# snc98_Display_15x7-Seg_1-digit_SC39.net
KiCad netlist of a schematic drawn in EAGLE
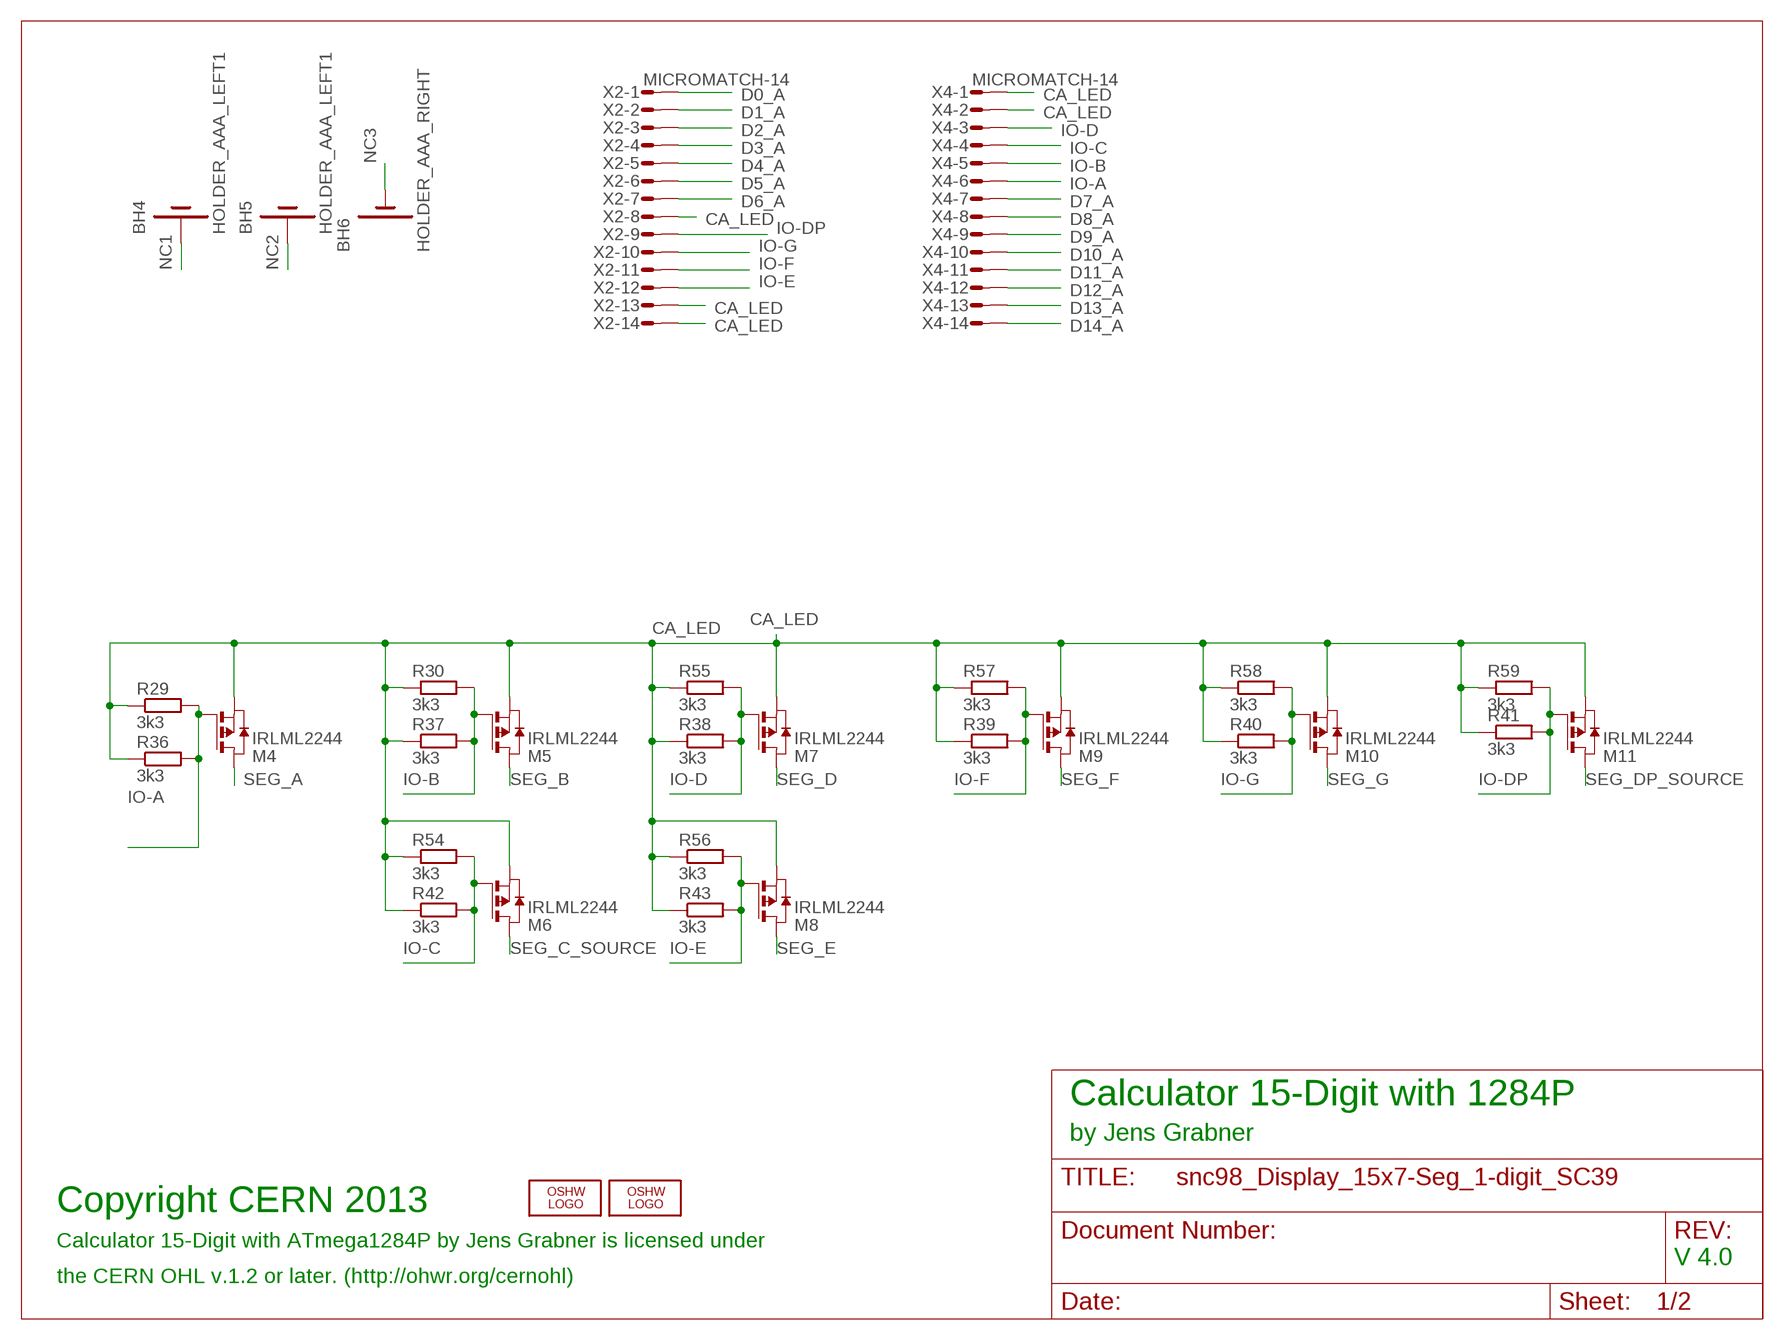
[diagram p0: schematic, sheet 1]
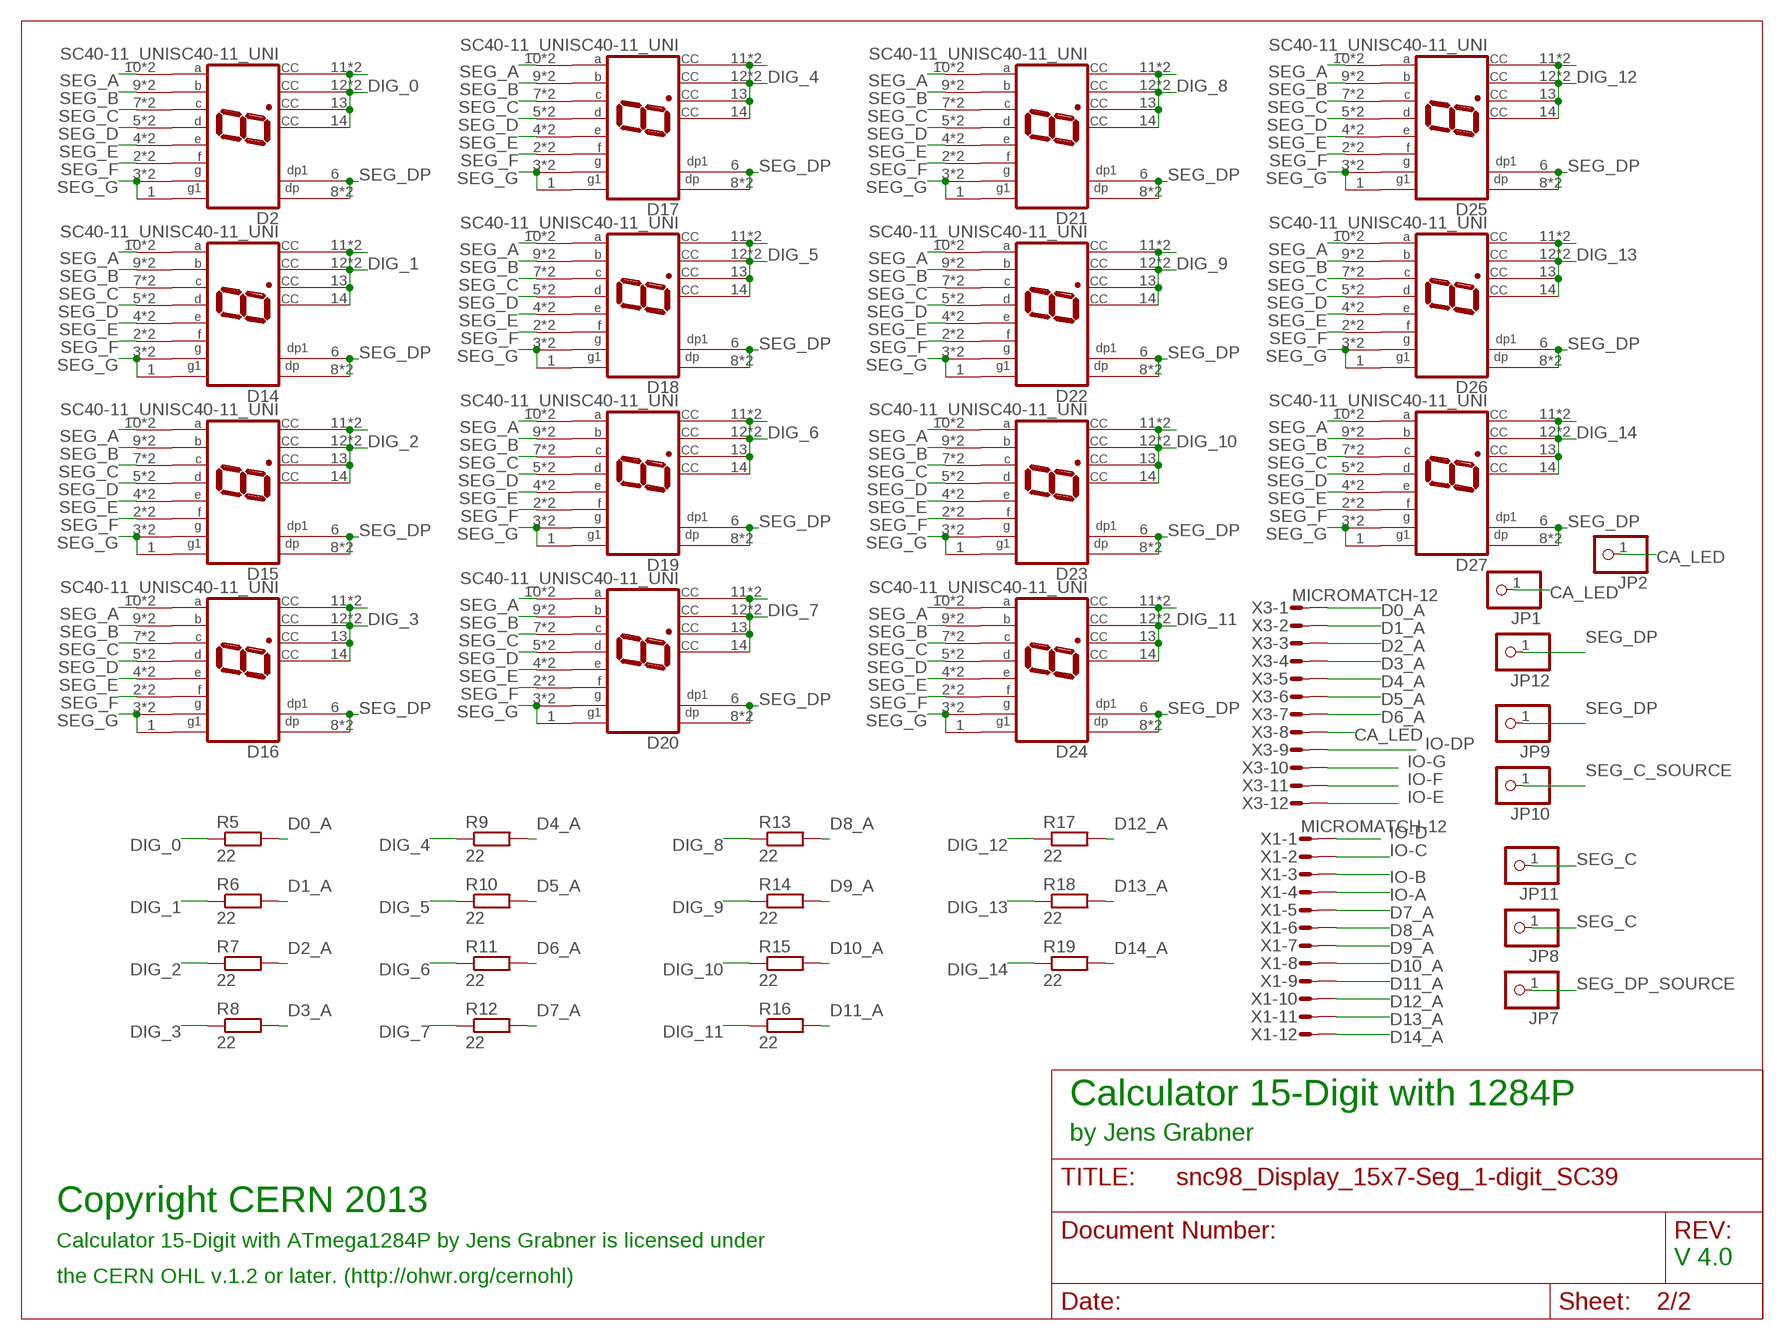
[diagram p1: schematic, sheet 2]

(export (version "E")
  (design (tool "Eeschema 10.0.6"))
  (components
    (comp (ref "D2")
      (value "SC40-11_UNISC40-11_UNI")
      (footprint "eagle-import:10MM_UNI")
      (libsource (lib "eagle-import") (part "SC40-11_UNISC40-11_UNI"))
    )
    (comp (ref "D14")
      (value "SC40-11_UNISC40-11_UNI")
      (footprint "eagle-import:10MM_UNI")
      (libsource (lib "eagle-import") (part "SC40-11_UNISC40-11_UNI"))
    )
    (comp (ref "D15")
      (value "SC40-11_UNISC40-11_UNI")
      (footprint "eagle-import:10MM_UNI")
      (libsource (lib "eagle-import") (part "SC40-11_UNISC40-11_UNI"))
    )
    (comp (ref "D16")
      (value "SC40-11_UNISC40-11_UNI")
      (footprint "eagle-import:10MM_UNI")
      (libsource (lib "eagle-import") (part "SC40-11_UNISC40-11_UNI"))
    )
    (comp (ref "D17")
      (value "SC40-11_UNISC40-11_UNI")
      (footprint "eagle-import:10MM_UNI")
      (libsource (lib "eagle-import") (part "SC40-11_UNISC40-11_UNI"))
    )
    (comp (ref "D18")
      (value "SC40-11_UNISC40-11_UNI")
      (footprint "eagle-import:10MM_UNI")
      (libsource (lib "eagle-import") (part "SC40-11_UNISC40-11_UNI"))
    )
    (comp (ref "D19")
      (value "SC40-11_UNISC40-11_UNI")
      (footprint "eagle-import:10MM_UNI")
      (libsource (lib "eagle-import") (part "SC40-11_UNISC40-11_UNI"))
    )
    (comp (ref "D20")
      (value "SC40-11_UNISC40-11_UNI")
      (footprint "eagle-import:10MM_UNI")
      (libsource (lib "eagle-import") (part "SC40-11_UNISC40-11_UNI"))
    )
    (comp (ref "D21")
      (value "SC40-11_UNISC40-11_UNI")
      (footprint "eagle-import:10MM_UNI")
      (libsource (lib "eagle-import") (part "SC40-11_UNISC40-11_UNI"))
    )
    (comp (ref "D22")
      (value "SC40-11_UNISC40-11_UNI")
      (footprint "eagle-import:10MM_UNI")
      (libsource (lib "eagle-import") (part "SC40-11_UNISC40-11_UNI"))
    )
    (comp (ref "D23")
      (value "SC40-11_UNISC40-11_UNI")
      (footprint "eagle-import:10MM_UNI")
      (libsource (lib "eagle-import") (part "SC40-11_UNISC40-11_UNI"))
    )
    (comp (ref "D24")
      (value "SC40-11_UNISC40-11_UNI")
      (footprint "eagle-import:10MM_UNI")
      (libsource (lib "eagle-import") (part "SC40-11_UNISC40-11_UNI"))
    )
    (comp (ref "D25")
      (value "SC40-11_UNISC40-11_UNI")
      (footprint "eagle-import:10MM_UNI")
      (libsource (lib "eagle-import") (part "SC40-11_UNISC40-11_UNI"))
    )
    (comp (ref "D26")
      (value "SC40-11_UNISC40-11_UNI")
      (footprint "eagle-import:10MM_UNI")
      (libsource (lib "eagle-import") (part "SC40-11_UNISC40-11_UNI"))
    )
    (comp (ref "D27")
      (value "SC40-11_UNISC40-11_UNI")
      (footprint "eagle-import:10MM_UNI")
      (libsource (lib "eagle-import") (part "SC40-11_UNISC40-11_UNI"))
    )
    (comp (ref "JP1")
      (value "PINHD-1X1")
      (footprint "eagle-import:1X01")
      (libsource (lib "eagle-import") (part "PINHD-1X1"))
    )
    (comp (ref "JP2")
      (value "PINHD-1X1")
      (footprint "eagle-import:1X01")
      (libsource (lib "eagle-import") (part "PINHD-1X1"))
    )
    (comp (ref "JP7")
      (value "PINHD-1X1")
      (footprint "eagle-import:1X01")
      (libsource (lib "eagle-import") (part "PINHD-1X1"))
    )
    (comp (ref "JP8")
      (value "PINHD-1X1")
      (footprint "eagle-import:1X01")
      (libsource (lib "eagle-import") (part "PINHD-1X1"))
    )
    (comp (ref "JP9")
      (value "PINHD-1X1")
      (footprint "eagle-import:1X01")
      (libsource (lib "eagle-import") (part "PINHD-1X1"))
    )
    (comp (ref "JP10")
      (value "PINHD-1X1")
      (footprint "eagle-import:1X01")
      (libsource (lib "eagle-import") (part "PINHD-1X1"))
    )
    (comp (ref "JP11")
      (value "PINHD-1X1")
      (footprint "eagle-import:1X01")
      (libsource (lib "eagle-import") (part "PINHD-1X1"))
    )
    (comp (ref "JP12")
      (value "PINHD-1X1")
      (footprint "eagle-import:1X01")
      (libsource (lib "eagle-import") (part "PINHD-1X1"))
    )
    (comp (ref "R5")
      (value "22")
      (footprint "eagle-import:R1210")
      (libsource (lib "eagle-import") (part "R-EU_R1210"))
    )
    (comp (ref "R6")
      (value "22")
      (footprint "eagle-import:R1210")
      (libsource (lib "eagle-import") (part "R-EU_R1210"))
    )
    (comp (ref "R7")
      (value "22")
      (footprint "eagle-import:R1210")
      (libsource (lib "eagle-import") (part "R-EU_R1210"))
    )
    (comp (ref "R8")
      (value "22")
      (footprint "eagle-import:R1210")
      (libsource (lib "eagle-import") (part "R-EU_R1210"))
    )
    (comp (ref "R9")
      (value "22")
      (footprint "eagle-import:R1210")
      (libsource (lib "eagle-import") (part "R-EU_R1210"))
    )
    (comp (ref "R10")
      (value "22")
      (footprint "eagle-import:R1210")
      (libsource (lib "eagle-import") (part "R-EU_R1210"))
    )
    (comp (ref "R11")
      (value "22")
      (footprint "eagle-import:R1210")
      (libsource (lib "eagle-import") (part "R-EU_R1210"))
    )
    (comp (ref "R12")
      (value "22")
      (footprint "eagle-import:R1210")
      (libsource (lib "eagle-import") (part "R-EU_R1210"))
    )
    (comp (ref "R13")
      (value "22")
      (footprint "eagle-import:R1210")
      (libsource (lib "eagle-import") (part "R-EU_R1210"))
    )
    (comp (ref "R14")
      (value "22")
      (footprint "eagle-import:R1210")
      (libsource (lib "eagle-import") (part "R-EU_R1210"))
    )
    (comp (ref "R15")
      (value "22")
      (footprint "eagle-import:R1210")
      (libsource (lib "eagle-import") (part "R-EU_R1210"))
    )
    (comp (ref "R16")
      (value "22")
      (footprint "eagle-import:R1210")
      (libsource (lib "eagle-import") (part "R-EU_R1210"))
    )
    (comp (ref "R17")
      (value "22")
      (footprint "eagle-import:R1210")
      (libsource (lib "eagle-import") (part "R-EU_R1210"))
    )
    (comp (ref "R18")
      (value "22")
      (footprint "eagle-import:R1210")
      (libsource (lib "eagle-import") (part "R-EU_R1210"))
    )
    (comp (ref "R19")
      (value "22")
      (footprint "eagle-import:R1210")
      (libsource (lib "eagle-import") (part "R-EU_R1210"))
    )
    (comp (ref "X1")
      (value "MICROMATCH-12")
      (footprint "eagle-import:MICROMATCH-12")
      (fields (field (name "MF") "FARNELL") (field (name "MPN") "8-215464-2"))
      (libsource (lib "eagle-import") (part "MICROMATCH-12"))
    )
    (comp (ref "X3")
      (value "MICROMATCH-12")
      (footprint "eagle-import:MICROMATCH-12")
      (fields (field (name "MF") "FARNELL") (field (name "MPN") "8-215464-2"))
      (libsource (lib "eagle-import") (part "MICROMATCH-12"))
    )
    (comp (ref "BH4")
      (value "HOLDER_AAA_LEFT1")
      (footprint "eagle-import:BATTERY-AAA-LEFT")
      (libsource (lib "eagle-import") (part "HOLDER_AAA_LEFT1"))
    )
    (comp (ref "BH5")
      (value "HOLDER_AAA_LEFT1")
      (footprint "eagle-import:BATTERY-AAA-LEFT")
      (libsource (lib "eagle-import") (part "HOLDER_AAA_LEFT1"))
    )
    (comp (ref "BH6")
      (value "HOLDER_AAA_RIGHT")
      (footprint "eagle-import:BATTERY-AAA-RIGHT")
      (libsource (lib "eagle-import") (part "HOLDER_AAA_RIGHT"))
    )
    (comp (ref "LOGO1")
      (value "OSHW_LOGO_8MILX0150-NT")
      (footprint "eagle-import:OSHW_8X150_NOTEXT")
      (libsource (lib "eagle-import") (part "OSHW_LOGO_8MILX0150-NT"))
    )
    (comp (ref "LOGO3")
      (value "OSHW_LOGO_6MILX0100-NT")
      (footprint "eagle-import:OSHW_6X100_NOTEXT")
      (libsource (lib "eagle-import") (part "OSHW_LOGO_6MILX0100-NT"))
    )
    (comp (ref "M4")
      (value "IRLML2244")
      (footprint "eagle-import:SOT-23")
      (libsource (lib "eagle-import") (part "IRLML6402"))
    )
    (comp (ref "M5")
      (value "IRLML2244")
      (footprint "eagle-import:SOT-23")
      (libsource (lib "eagle-import") (part "IRLML6402"))
    )
    (comp (ref "M6")
      (value "IRLML2244")
      (footprint "eagle-import:SOT-23")
      (libsource (lib "eagle-import") (part "IRLML6402"))
    )
    (comp (ref "M7")
      (value "IRLML2244")
      (footprint "eagle-import:SOT-23")
      (libsource (lib "eagle-import") (part "IRLML6402"))
    )
    (comp (ref "M8")
      (value "IRLML2244")
      (footprint "eagle-import:SOT-23")
      (libsource (lib "eagle-import") (part "IRLML6402"))
    )
    (comp (ref "M9")
      (value "IRLML2244")
      (footprint "eagle-import:SOT-23")
      (libsource (lib "eagle-import") (part "IRLML6402"))
    )
    (comp (ref "M10")
      (value "IRLML2244")
      (footprint "eagle-import:SOT-23")
      (libsource (lib "eagle-import") (part "IRLML6402"))
    )
    (comp (ref "M11")
      (value "IRLML2244")
      (footprint "eagle-import:SOT-23")
      (libsource (lib "eagle-import") (part "IRLML6402"))
    )
    (comp (ref "R29")
      (value "3k3")
      (footprint "eagle-import:0204_5")
      (libsource (lib "eagle-import") (part "R-EU_0204/5"))
    )
    (comp (ref "R30")
      (value "3k3")
      (footprint "eagle-import:0204_5")
      (libsource (lib "eagle-import") (part "R-EU_0204/5"))
    )
    (comp (ref "R36")
      (value "3k3")
      (footprint "eagle-import:R1206")
      (libsource (lib "eagle-import") (part "R-EU_R1206"))
    )
    (comp (ref "R37")
      (value "3k3")
      (footprint "eagle-import:R1206")
      (libsource (lib "eagle-import") (part "R-EU_R1206"))
    )
    (comp (ref "R38")
      (value "3k3")
      (footprint "eagle-import:R1206")
      (libsource (lib "eagle-import") (part "R-EU_R1206"))
    )
    (comp (ref "R39")
      (value "3k3")
      (footprint "eagle-import:R1206")
      (libsource (lib "eagle-import") (part "R-EU_R1206"))
    )
    (comp (ref "R40")
      (value "3k3")
      (footprint "eagle-import:R1206")
      (libsource (lib "eagle-import") (part "R-EU_R1206"))
    )
    (comp (ref "R41")
      (value "3k3")
      (footprint "eagle-import:R1206")
      (libsource (lib "eagle-import") (part "R-EU_R1206"))
    )
    (comp (ref "R42")
      (value "3k3")
      (footprint "eagle-import:R1206")
      (libsource (lib "eagle-import") (part "R-EU_R1206"))
    )
    (comp (ref "R43")
      (value "3k3")
      (footprint "eagle-import:R1206")
      (libsource (lib "eagle-import") (part "R-EU_R1206"))
    )
    (comp (ref "R54")
      (value "3k3")
      (footprint "eagle-import:0204_5")
      (libsource (lib "eagle-import") (part "R-EU_0204/5"))
    )
    (comp (ref "R55")
      (value "3k3")
      (footprint "eagle-import:0204_5")
      (libsource (lib "eagle-import") (part "R-EU_0204/5"))
    )
    (comp (ref "R56")
      (value "3k3")
      (footprint "eagle-import:0204_5")
      (libsource (lib "eagle-import") (part "R-EU_0204/5"))
    )
    (comp (ref "R57")
      (value "3k3")
      (footprint "eagle-import:0204_5")
      (libsource (lib "eagle-import") (part "R-EU_0204/5"))
    )
    (comp (ref "R58")
      (value "3k3")
      (footprint "eagle-import:0204_5")
      (libsource (lib "eagle-import") (part "R-EU_0204/5"))
    )
    (comp (ref "R59")
      (value "3k3")
      (footprint "eagle-import:0204_5")
      (libsource (lib "eagle-import") (part "R-EU_0204/5"))
    )
    (comp (ref "X2")
      (value "MICROMATCH-14")
      (footprint "eagle-import:MICROMATCH-14")
      (fields (field (name "MF") "FARNELL") (field (name "MPN") "8-215464-4"))
      (libsource (lib "eagle-import") (part "MICROMATCH-14"))
    )
    (comp (ref "X4")
      (value "MICROMATCH-14")
      (footprint "eagle-import:MICROMATCH-14")
      (fields (field (name "MF") "FARNELL") (field (name "MPN") "8-215464-4"))
      (libsource (lib "eagle-import") (part "MICROMATCH-14"))
    )
  )
  (nets
    (net (code "1") (name "CA_LED") (class "Default")
      (node (ref "JP1") (pin "1") (pinfunction "1_1") (pintype "passive"))
      (node (ref "JP2") (pin "1") (pinfunction "1_1") (pintype "passive"))
      (node (ref "M10") (pin "2") (pinfunction "S_2") (pintype "passive"))
      (node (ref "M11") (pin "2") (pinfunction "S_2") (pintype "passive"))
      (node (ref "M4") (pin "2") (pinfunction "S_2") (pintype "passive"))
      (node (ref "M5") (pin "2") (pinfunction "S_2") (pintype "passive"))
      (node (ref "M6") (pin "2") (pinfunction "S_2") (pintype "passive"))
      (node (ref "M7") (pin "2") (pinfunction "S_2") (pintype "passive"))
      (node (ref "M8") (pin "2") (pinfunction "S_2") (pintype "passive"))
      (node (ref "M9") (pin "2") (pinfunction "S_2") (pintype "passive"))
      (node (ref "R29") (pin "1") (pinfunction "1_1") (pintype "passive"))
      (node (ref "R30") (pin "1") (pinfunction "1_1") (pintype "passive"))
      (node (ref "R36") (pin "1") (pinfunction "1_1") (pintype "passive"))
      (node (ref "R37") (pin "1") (pinfunction "1_1") (pintype "passive"))
      (node (ref "R38") (pin "1") (pinfunction "1_1") (pintype "passive"))
      (node (ref "R39") (pin "1") (pinfunction "1_1") (pintype "passive"))
      (node (ref "R40") (pin "1") (pinfunction "1_1") (pintype "passive"))
      (node (ref "R41") (pin "1") (pinfunction "1_1") (pintype "passive"))
      (node (ref "R42") (pin "1") (pinfunction "1_1") (pintype "passive"))
      (node (ref "R43") (pin "1") (pinfunction "1_1") (pintype "passive"))
      (node (ref "R54") (pin "1") (pinfunction "1_1") (pintype "passive"))
      (node (ref "R55") (pin "1") (pinfunction "1_1") (pintype "passive"))
      (node (ref "R56") (pin "1") (pinfunction "1_1") (pintype "passive"))
      (node (ref "R57") (pin "1") (pinfunction "1_1") (pintype "passive"))
      (node (ref "R58") (pin "1") (pinfunction "1_1") (pintype "passive"))
      (node (ref "R59") (pin "1") (pinfunction "1_1") (pintype "passive"))
      (node (ref "X2") (pin "13") (pinfunction "S_13") (pintype "passive"))
      (node (ref "X2") (pin "14") (pinfunction "S_14") (pintype "passive"))
      (node (ref "X2") (pin "8") (pinfunction "S_8") (pintype "passive"))
      (node (ref "X3") (pin "8") (pinfunction "S_8") (pintype "passive"))
      (node (ref "X4") (pin "1") (pinfunction "S_1") (pintype "passive"))
      (node (ref "X4") (pin "2") (pinfunction "S_2") (pintype "passive"))
    )
    (net (code "2") (name "D0_A") (class "Default")
      (node (ref "R5") (pin "2") (pinfunction "2_2") (pintype "passive"))
      (node (ref "X2") (pin "1") (pinfunction "S_1") (pintype "passive"))
      (node (ref "X3") (pin "1") (pinfunction "S_1") (pintype "passive"))
    )
    (net (code "3") (name "D1_A") (class "Default")
      (node (ref "R6") (pin "2") (pinfunction "2_2") (pintype "passive"))
      (node (ref "X2") (pin "2") (pinfunction "S_2") (pintype "passive"))
      (node (ref "X3") (pin "2") (pinfunction "S_2") (pintype "passive"))
    )
    (net (code "4") (name "D2_A") (class "Default")
      (node (ref "R7") (pin "2") (pinfunction "2_2") (pintype "passive"))
      (node (ref "X2") (pin "3") (pinfunction "S_3") (pintype "passive"))
      (node (ref "X3") (pin "3") (pinfunction "S_3") (pintype "passive"))
    )
    (net (code "5") (name "D3_A") (class "Default")
      (node (ref "R8") (pin "2") (pinfunction "2_2") (pintype "passive"))
      (node (ref "X2") (pin "4") (pinfunction "S_4") (pintype "passive"))
      (node (ref "X3") (pin "4") (pinfunction "S_4") (pintype "passive"))
    )
    (net (code "6") (name "D4_A") (class "Default")
      (node (ref "R9") (pin "2") (pinfunction "2_2") (pintype "passive"))
      (node (ref "X2") (pin "5") (pinfunction "S_5") (pintype "passive"))
      (node (ref "X3") (pin "5") (pinfunction "S_5") (pintype "passive"))
    )
    (net (code "7") (name "D5_A") (class "Default")
      (node (ref "R10") (pin "2") (pinfunction "2_2") (pintype "passive"))
      (node (ref "X2") (pin "6") (pinfunction "S_6") (pintype "passive"))
      (node (ref "X3") (pin "6") (pinfunction "S_6") (pintype "passive"))
    )
    (net (code "8") (name "D6_A") (class "Default")
      (node (ref "R11") (pin "2") (pinfunction "2_2") (pintype "passive"))
      (node (ref "X2") (pin "7") (pinfunction "S_7") (pintype "passive"))
      (node (ref "X3") (pin "7") (pinfunction "S_7") (pintype "passive"))
    )
    (net (code "9") (name "D7_A") (class "Default")
      (node (ref "R12") (pin "2") (pinfunction "2_2") (pintype "passive"))
      (node (ref "X1") (pin "5") (pinfunction "S_5") (pintype "passive"))
      (node (ref "X4") (pin "7") (pinfunction "S_7") (pintype "passive"))
    )
    (net (code "10") (name "D8_A") (class "Default")
      (node (ref "R13") (pin "2") (pinfunction "2_2") (pintype "passive"))
      (node (ref "X1") (pin "6") (pinfunction "S_6") (pintype "passive"))
      (node (ref "X4") (pin "8") (pinfunction "S_8") (pintype "passive"))
    )
    (net (code "11") (name "D9_A") (class "Default")
      (node (ref "R14") (pin "2") (pinfunction "2_2") (pintype "passive"))
      (node (ref "X1") (pin "7") (pinfunction "S_7") (pintype "passive"))
      (node (ref "X4") (pin "9") (pinfunction "S_9") (pintype "passive"))
    )
    (net (code "12") (name "D10_A") (class "Default")
      (node (ref "R15") (pin "2") (pinfunction "2_2") (pintype "passive"))
      (node (ref "X1") (pin "8") (pinfunction "S_8") (pintype "passive"))
      (node (ref "X4") (pin "10") (pinfunction "S_10") (pintype "passive"))
    )
    (net (code "13") (name "D11_A") (class "Default")
      (node (ref "R16") (pin "2") (pinfunction "2_2") (pintype "passive"))
      (node (ref "X1") (pin "9") (pinfunction "S_9") (pintype "passive"))
      (node (ref "X4") (pin "11") (pinfunction "S_11") (pintype "passive"))
    )
    (net (code "14") (name "D12_A") (class "Default")
      (node (ref "R17") (pin "2") (pinfunction "2_2") (pintype "passive"))
      (node (ref "X1") (pin "10") (pinfunction "S_10") (pintype "passive"))
      (node (ref "X4") (pin "12") (pinfunction "S_12") (pintype "passive"))
    )
    (net (code "15") (name "D13_A") (class "Default")
      (node (ref "R18") (pin "2") (pinfunction "2_2") (pintype "passive"))
      (node (ref "X1") (pin "11") (pinfunction "S_11") (pintype "passive"))
      (node (ref "X4") (pin "13") (pinfunction "S_13") (pintype "passive"))
    )
    (net (code "16") (name "D14_A") (class "Default")
      (node (ref "R19") (pin "2") (pinfunction "2_2") (pintype "passive"))
      (node (ref "X1") (pin "12") (pinfunction "S_12") (pintype "passive"))
      (node (ref "X4") (pin "14") (pinfunction "S_14") (pintype "passive"))
    )
    (net (code "17") (name "DIG_0") (class "Default")
      (node (ref "D2") (pin "11") (pinfunction "CC1_11") (pintype "passive"))
      (node (ref "D2") (pin "12") (pinfunction "CC2_12") (pintype "passive"))
      (node (ref "D2") (pin "13") (pinfunction "CC3_13") (pintype "passive"))
      (node (ref "D2") (pin "14") (pinfunction "CC4_14") (pintype "passive"))
      (node (ref "D2") (pin "23") (pinfunction "CC1_23") (pintype "passive"))
      (node (ref "D2") (pin "28") (pinfunction "CC2_28") (pintype "passive"))
      (node (ref "R5") (pin "1") (pinfunction "1_1") (pintype "passive"))
    )
    (net (code "18") (name "DIG_1") (class "Default")
      (node (ref "D14") (pin "11") (pinfunction "CC1_11") (pintype "passive"))
      (node (ref "D14") (pin "12") (pinfunction "CC2_12") (pintype "passive"))
      (node (ref "D14") (pin "13") (pinfunction "CC3_13") (pintype "passive"))
      (node (ref "D14") (pin "14") (pinfunction "CC4_14") (pintype "passive"))
      (node (ref "D14") (pin "23") (pinfunction "CC1_23") (pintype "passive"))
      (node (ref "D14") (pin "28") (pinfunction "CC2_28") (pintype "passive"))
      (node (ref "R6") (pin "1") (pinfunction "1_1") (pintype "passive"))
    )
    (net (code "19") (name "DIG_2") (class "Default")
      (node (ref "D15") (pin "11") (pinfunction "CC1_11") (pintype "passive"))
      (node (ref "D15") (pin "12") (pinfunction "CC2_12") (pintype "passive"))
      (node (ref "D15") (pin "13") (pinfunction "CC3_13") (pintype "passive"))
      (node (ref "D15") (pin "14") (pinfunction "CC4_14") (pintype "passive"))
      (node (ref "D15") (pin "23") (pinfunction "CC1_23") (pintype "passive"))
      (node (ref "D15") (pin "28") (pinfunction "CC2_28") (pintype "passive"))
      (node (ref "R7") (pin "1") (pinfunction "1_1") (pintype "passive"))
    )
    (net (code "20") (name "DIG_3") (class "Default")
      (node (ref "D16") (pin "11") (pinfunction "CC1_11") (pintype "passive"))
      (node (ref "D16") (pin "12") (pinfunction "CC2_12") (pintype "passive"))
      (node (ref "D16") (pin "13") (pinfunction "CC3_13") (pintype "passive"))
      (node (ref "D16") (pin "14") (pinfunction "CC4_14") (pintype "passive"))
      (node (ref "D16") (pin "23") (pinfunction "CC1_23") (pintype "passive"))
      (node (ref "D16") (pin "28") (pinfunction "CC2_28") (pintype "passive"))
      (node (ref "R8") (pin "1") (pinfunction "1_1") (pintype "passive"))
    )
    (net (code "21") (name "DIG_4") (class "Default")
      (node (ref "D17") (pin "11") (pinfunction "CC1_11") (pintype "passive"))
      (node (ref "D17") (pin "12") (pinfunction "CC2_12") (pintype "passive"))
      (node (ref "D17") (pin "13") (pinfunction "CC3_13") (pintype "passive"))
      (node (ref "D17") (pin "14") (pinfunction "CC4_14") (pintype "passive"))
      (node (ref "D17") (pin "23") (pinfunction "CC1_23") (pintype "passive"))
      (node (ref "D17") (pin "28") (pinfunction "CC2_28") (pintype "passive"))
      (node (ref "R9") (pin "1") (pinfunction "1_1") (pintype "passive"))
    )
    (net (code "22") (name "DIG_5") (class "Default")
      (node (ref "D18") (pin "11") (pinfunction "CC1_11") (pintype "passive"))
      (node (ref "D18") (pin "12") (pinfunction "CC2_12") (pintype "passive"))
      (node (ref "D18") (pin "13") (pinfunction "CC3_13") (pintype "passive"))
      (node (ref "D18") (pin "14") (pinfunction "CC4_14") (pintype "passive"))
      (node (ref "D18") (pin "23") (pinfunction "CC1_23") (pintype "passive"))
      (node (ref "D18") (pin "28") (pinfunction "CC2_28") (pintype "passive"))
      (node (ref "R10") (pin "1") (pinfunction "1_1") (pintype "passive"))
    )
    (net (code "23") (name "DIG_6") (class "Default")
      (node (ref "D19") (pin "11") (pinfunction "CC1_11") (pintype "passive"))
      (node (ref "D19") (pin "12") (pinfunction "CC2_12") (pintype "passive"))
      (node (ref "D19") (pin "13") (pinfunction "CC3_13") (pintype "passive"))
      (node (ref "D19") (pin "14") (pinfunction "CC4_14") (pintype "passive"))
      (node (ref "D19") (pin "23") (pinfunction "CC1_23") (pintype "passive"))
      (node (ref "D19") (pin "28") (pinfunction "CC2_28") (pintype "passive"))
      (node (ref "R11") (pin "1") (pinfunction "1_1") (pintype "passive"))
    )
    (net (code "24") (name "DIG_7") (class "Default")
      (node (ref "D20") (pin "11") (pinfunction "CC1_11") (pintype "passive"))
      (node (ref "D20") (pin "12") (pinfunction "CC2_12") (pintype "passive"))
      (node (ref "D20") (pin "13") (pinfunction "CC3_13") (pintype "passive"))
      (node (ref "D20") (pin "14") (pinfunction "CC4_14") (pintype "passive"))
      (node (ref "D20") (pin "23") (pinfunction "CC1_23") (pintype "passive"))
      (node (ref "D20") (pin "28") (pinfunction "CC2_28") (pintype "passive"))
      (node (ref "R12") (pin "1") (pinfunction "1_1") (pintype "passive"))
    )
    (net (code "25") (name "DIG_8") (class "Default")
      (node (ref "D21") (pin "11") (pinfunction "CC1_11") (pintype "passive"))
      (node (ref "D21") (pin "12") (pinfunction "CC2_12") (pintype "passive"))
      (node (ref "D21") (pin "13") (pinfunction "CC3_13") (pintype "passive"))
      (node (ref "D21") (pin "14") (pinfunction "CC4_14") (pintype "passive"))
      (node (ref "D21") (pin "23") (pinfunction "CC1_23") (pintype "passive"))
      (node (ref "D21") (pin "28") (pinfunction "CC2_28") (pintype "passive"))
      (node (ref "R13") (pin "1") (pinfunction "1_1") (pintype "passive"))
    )
    (net (code "26") (name "DIG_9") (class "Default")
      (node (ref "D22") (pin "11") (pinfunction "CC1_11") (pintype "passive"))
      (node (ref "D22") (pin "12") (pinfunction "CC2_12") (pintype "passive"))
      (node (ref "D22") (pin "13") (pinfunction "CC3_13") (pintype "passive"))
      (node (ref "D22") (pin "14") (pinfunction "CC4_14") (pintype "passive"))
      (node (ref "D22") (pin "23") (pinfunction "CC1_23") (pintype "passive"))
      (node (ref "D22") (pin "28") (pinfunction "CC2_28") (pintype "passive"))
      (node (ref "R14") (pin "1") (pinfunction "1_1") (pintype "passive"))
    )
    (net (code "27") (name "DIG_10") (class "Default")
      (node (ref "D23") (pin "11") (pinfunction "CC1_11") (pintype "passive"))
      (node (ref "D23") (pin "12") (pinfunction "CC2_12") (pintype "passive"))
      (node (ref "D23") (pin "13") (pinfunction "CC3_13") (pintype "passive"))
      (node (ref "D23") (pin "14") (pinfunction "CC4_14") (pintype "passive"))
      (node (ref "D23") (pin "23") (pinfunction "CC1_23") (pintype "passive"))
      (node (ref "D23") (pin "28") (pinfunction "CC2_28") (pintype "passive"))
      (node (ref "R15") (pin "1") (pinfunction "1_1") (pintype "passive"))
    )
    (net (code "28") (name "DIG_11") (class "Default")
      (node (ref "D24") (pin "11") (pinfunction "CC1_11") (pintype "passive"))
      (node (ref "D24") (pin "12") (pinfunction "CC2_12") (pintype "passive"))
      (node (ref "D24") (pin "13") (pinfunction "CC3_13") (pintype "passive"))
      (node (ref "D24") (pin "14") (pinfunction "CC4_14") (pintype "passive"))
      (node (ref "D24") (pin "23") (pinfunction "CC1_23") (pintype "passive"))
      (node (ref "D24") (pin "28") (pinfunction "CC2_28") (pintype "passive"))
      (node (ref "R16") (pin "1") (pinfunction "1_1") (pintype "passive"))
    )
    (net (code "29") (name "DIG_12") (class "Default")
      (node (ref "D25") (pin "11") (pinfunction "CC1_11") (pintype "passive"))
      (node (ref "D25") (pin "12") (pinfunction "CC2_12") (pintype "passive"))
      (node (ref "D25") (pin "13") (pinfunction "CC3_13") (pintype "passive"))
      (node (ref "D25") (pin "14") (pinfunction "CC4_14") (pintype "passive"))
      (node (ref "D25") (pin "23") (pinfunction "CC1_23") (pintype "passive"))
      (node (ref "D25") (pin "28") (pinfunction "CC2_28") (pintype "passive"))
      (node (ref "R17") (pin "1") (pinfunction "1_1") (pintype "passive"))
    )
    (net (code "30") (name "DIG_13") (class "Default")
      (node (ref "D26") (pin "11") (pinfunction "CC1_11") (pintype "passive"))
      (node (ref "D26") (pin "12") (pinfunction "CC2_12") (pintype "passive"))
      (node (ref "D26") (pin "13") (pinfunction "CC3_13") (pintype "passive"))
      (node (ref "D26") (pin "14") (pinfunction "CC4_14") (pintype "passive"))
      (node (ref "D26") (pin "23") (pinfunction "CC1_23") (pintype "passive"))
      (node (ref "D26") (pin "28") (pinfunction "CC2_28") (pintype "passive"))
      (node (ref "R18") (pin "1") (pinfunction "1_1") (pintype "passive"))
    )
    (net (code "31") (name "DIG_14") (class "Default")
      (node (ref "D27") (pin "11") (pinfunction "CC1_11") (pintype "passive"))
      (node (ref "D27") (pin "12") (pinfunction "CC2_12") (pintype "passive"))
      (node (ref "D27") (pin "13") (pinfunction "CC3_13") (pintype "passive"))
      (node (ref "D27") (pin "14") (pinfunction "CC4_14") (pintype "passive"))
      (node (ref "D27") (pin "23") (pinfunction "CC1_23") (pintype "passive"))
      (node (ref "D27") (pin "28") (pinfunction "CC2_28") (pintype "passive"))
      (node (ref "R19") (pin "1") (pinfunction "1_1") (pintype "passive"))
    )
    (net (code "32") (name "IO-A") (class "Default")
      (node (ref "M4") (pin "1") (pinfunction "G_1") (pintype "passive"))
      (node (ref "R29") (pin "2") (pinfunction "2_2") (pintype "passive"))
      (node (ref "R36") (pin "2") (pinfunction "2_2") (pintype "passive"))
      (node (ref "X1") (pin "4") (pinfunction "S_4") (pintype "passive"))
      (node (ref "X4") (pin "6") (pinfunction "S_6") (pintype "passive"))
    )
    (net (code "33") (name "IO-B") (class "Default")
      (node (ref "M5") (pin "1") (pinfunction "G_1") (pintype "passive"))
      (node (ref "R30") (pin "2") (pinfunction "2_2") (pintype "passive"))
      (node (ref "R37") (pin "2") (pinfunction "2_2") (pintype "passive"))
      (node (ref "X1") (pin "3") (pinfunction "S_3") (pintype "passive"))
      (node (ref "X4") (pin "5") (pinfunction "S_5") (pintype "passive"))
    )
    (net (code "34") (name "IO-C") (class "Default")
      (node (ref "M6") (pin "1") (pinfunction "G_1") (pintype "passive"))
      (node (ref "R42") (pin "2") (pinfunction "2_2") (pintype "passive"))
      (node (ref "R54") (pin "2") (pinfunction "2_2") (pintype "passive"))
      (node (ref "X1") (pin "2") (pinfunction "S_2") (pintype "passive"))
      (node (ref "X4") (pin "4") (pinfunction "S_4") (pintype "passive"))
    )
    (net (code "35") (name "IO-D") (class "Default")
      (node (ref "M7") (pin "1") (pinfunction "G_1") (pintype "passive"))
      (node (ref "R38") (pin "2") (pinfunction "2_2") (pintype "passive"))
      (node (ref "R55") (pin "2") (pinfunction "2_2") (pintype "passive"))
      (node (ref "X1") (pin "1") (pinfunction "S_1") (pintype "passive"))
      (node (ref "X4") (pin "3") (pinfunction "S_3") (pintype "passive"))
    )
    (net (code "36") (name "IO-DP") (class "Default")
      (node (ref "M11") (pin "1") (pinfunction "G_1") (pintype "passive"))
      (node (ref "R41") (pin "2") (pinfunction "2_2") (pintype "passive"))
      (node (ref "R59") (pin "2") (pinfunction "2_2") (pintype "passive"))
      (node (ref "X2") (pin "9") (pinfunction "S_9") (pintype "passive"))
      (node (ref "X3") (pin "9") (pinfunction "S_9") (pintype "passive"))
    )
    (net (code "37") (name "IO-E") (class "Default")
      (node (ref "M8") (pin "1") (pinfunction "G_1") (pintype "passive"))
      (node (ref "R43") (pin "2") (pinfunction "2_2") (pintype "passive"))
      (node (ref "R56") (pin "2") (pinfunction "2_2") (pintype "passive"))
      (node (ref "X2") (pin "12") (pinfunction "S_12") (pintype "passive"))
      (node (ref "X3") (pin "12") (pinfunction "S_12") (pintype "passive"))
    )
    (net (code "38") (name "IO-F") (class "Default")
      (node (ref "M9") (pin "1") (pinfunction "G_1") (pintype "passive"))
      (node (ref "R39") (pin "2") (pinfunction "2_2") (pintype "passive"))
      (node (ref "R57") (pin "2") (pinfunction "2_2") (pintype "passive"))
      (node (ref "X2") (pin "11") (pinfunction "S_11") (pintype "passive"))
      (node (ref "X3") (pin "11") (pinfunction "S_11") (pintype "passive"))
    )
    (net (code "39") (name "IO-G") (class "Default")
      (node (ref "M10") (pin "1") (pinfunction "G_1") (pintype "passive"))
      (node (ref "R40") (pin "2") (pinfunction "2_2") (pintype "passive"))
      (node (ref "R58") (pin "2") (pinfunction "2_2") (pintype "passive"))
      (node (ref "X2") (pin "10") (pinfunction "S_10") (pintype "passive"))
      (node (ref "X3") (pin "10") (pinfunction "S_10") (pintype "passive"))
    )
    (net (code "40") (name "NC1") (class "Default")
      (node (ref "BH4") (pin "P1") (pinfunction "+_P1") (pintype "power_in"))
      (node (ref "BH4") (pin "P2") (pinfunction "+_P2") (pintype "power_in"))
      (node (ref "BH4") (pin "P3") (pinfunction "+_P3") (pintype "power_in"))
      (node (ref "BH4") (pin "P4") (pinfunction "+_P4") (pintype "power_in"))
    )
    (net (code "41") (name "NC2") (class "Default")
      (node (ref "BH5") (pin "P1") (pinfunction "+_P1") (pintype "power_in"))
      (node (ref "BH5") (pin "P2") (pinfunction "+_P2") (pintype "power_in"))
      (node (ref "BH5") (pin "P3") (pinfunction "+_P3") (pintype "power_in"))
      (node (ref "BH5") (pin "P4") (pinfunction "+_P4") (pintype "power_in"))
    )
    (net (code "42") (name "NC3") (class "Default")
      (node (ref "BH6") (pin "M1") (pinfunction "-_M1") (pintype "power_in"))
      (node (ref "BH6") (pin "M2") (pinfunction "-_M2") (pintype "power_in"))
      (node (ref "BH6") (pin "M3") (pinfunction "-_M3") (pintype "power_in"))
      (node (ref "BH6") (pin "M4") (pinfunction "-_M4") (pintype "power_in"))
    )
    (net (code "43") (name "SEG_A") (class "Default")
      (node (ref "D14") (pin "10") (pinfunction "A_10") (pintype "passive"))
      (node (ref "D14") (pin "27") (pinfunction "A_27") (pintype "passive"))
      (node (ref "D15") (pin "10") (pinfunction "A_10") (pintype "passive"))
      (node (ref "D15") (pin "27") (pinfunction "A_27") (pintype "passive"))
      (node (ref "D16") (pin "10") (pinfunction "A_10") (pintype "passive"))
      (node (ref "D16") (pin "27") (pinfunction "A_27") (pintype "passive"))
      (node (ref "D17") (pin "10") (pinfunction "A_10") (pintype "passive"))
      (node (ref "D17") (pin "27") (pinfunction "A_27") (pintype "passive"))
      (node (ref "D18") (pin "10") (pinfunction "A_10") (pintype "passive"))
      (node (ref "D18") (pin "27") (pinfunction "A_27") (pintype "passive"))
      (node (ref "D19") (pin "10") (pinfunction "A_10") (pintype "passive"))
      (node (ref "D19") (pin "27") (pinfunction "A_27") (pintype "passive"))
      (node (ref "D2") (pin "10") (pinfunction "A_10") (pintype "passive"))
      (node (ref "D2") (pin "27") (pinfunction "A_27") (pintype "passive"))
      (node (ref "D20") (pin "10") (pinfunction "A_10") (pintype "passive"))
      (node (ref "D20") (pin "27") (pinfunction "A_27") (pintype "passive"))
      (node (ref "D21") (pin "10") (pinfunction "A_10") (pintype "passive"))
      (node (ref "D21") (pin "27") (pinfunction "A_27") (pintype "passive"))
      (node (ref "D22") (pin "10") (pinfunction "A_10") (pintype "passive"))
      (node (ref "D22") (pin "27") (pinfunction "A_27") (pintype "passive"))
      (node (ref "D23") (pin "10") (pinfunction "A_10") (pintype "passive"))
      (node (ref "D23") (pin "27") (pinfunction "A_27") (pintype "passive"))
      (node (ref "D24") (pin "10") (pinfunction "A_10") (pintype "passive"))
      (node (ref "D24") (pin "27") (pinfunction "A_27") (pintype "passive"))
      (node (ref "D25") (pin "10") (pinfunction "A_10") (pintype "passive"))
      (node (ref "D25") (pin "27") (pinfunction "A_27") (pintype "passive"))
      (node (ref "D26") (pin "10") (pinfunction "A_10") (pintype "passive"))
      (node (ref "D26") (pin "27") (pinfunction "A_27") (pintype "passive"))
      (node (ref "D27") (pin "10") (pinfunction "A_10") (pintype "passive"))
      (node (ref "D27") (pin "27") (pinfunction "A_27") (pintype "passive"))
      (node (ref "M4") (pin "3") (pinfunction "D_3") (pintype "passive"))
    )
    (net (code "44") (name "SEG_B") (class "Default")
      (node (ref "D14") (pin "26") (pinfunction "B_26") (pintype "passive"))
      (node (ref "D14") (pin "9") (pinfunction "B_9") (pintype "passive"))
      (node (ref "D15") (pin "26") (pinfunction "B_26") (pintype "passive"))
      (node (ref "D15") (pin "9") (pinfunction "B_9") (pintype "passive"))
      (node (ref "D16") (pin "26") (pinfunction "B_26") (pintype "passive"))
      (node (ref "D16") (pin "9") (pinfunction "B_9") (pintype "passive"))
      (node (ref "D17") (pin "26") (pinfunction "B_26") (pintype "passive"))
      (node (ref "D17") (pin "9") (pinfunction "B_9") (pintype "passive"))
      (node (ref "D18") (pin "26") (pinfunction "B_26") (pintype "passive"))
      (node (ref "D18") (pin "9") (pinfunction "B_9") (pintype "passive"))
      (node (ref "D19") (pin "26") (pinfunction "B_26") (pintype "passive"))
      (node (ref "D19") (pin "9") (pinfunction "B_9") (pintype "passive"))
      (node (ref "D2") (pin "26") (pinfunction "B_26") (pintype "passive"))
      (node (ref "D2") (pin "9") (pinfunction "B_9") (pintype "passive"))
      (node (ref "D20") (pin "26") (pinfunction "B_26") (pintype "passive"))
      (node (ref "D20") (pin "9") (pinfunction "B_9") (pintype "passive"))
      (node (ref "D21") (pin "26") (pinfunction "B_26") (pintype "passive"))
      (node (ref "D21") (pin "9") (pinfunction "B_9") (pintype "passive"))
      (node (ref "D22") (pin "26") (pinfunction "B_26") (pintype "passive"))
      (node (ref "D22") (pin "9") (pinfunction "B_9") (pintype "passive"))
      (node (ref "D23") (pin "26") (pinfunction "B_26") (pintype "passive"))
      (node (ref "D23") (pin "9") (pinfunction "B_9") (pintype "passive"))
      (node (ref "D24") (pin "26") (pinfunction "B_26") (pintype "passive"))
      (node (ref "D24") (pin "9") (pinfunction "B_9") (pintype "passive"))
      (node (ref "D25") (pin "26") (pinfunction "B_26") (pintype "passive"))
      (node (ref "D25") (pin "9") (pinfunction "B_9") (pintype "passive"))
      (node (ref "D26") (pin "26") (pinfunction "B_26") (pintype "passive"))
      (node (ref "D26") (pin "9") (pinfunction "B_9") (pintype "passive"))
      (node (ref "D27") (pin "26") (pinfunction "B_26") (pintype "passive"))
      (node (ref "D27") (pin "9") (pinfunction "B_9") (pintype "passive"))
      (node (ref "M5") (pin "3") (pinfunction "D_3") (pintype "passive"))
    )
    (net (code "45") (name "SEG_C") (class "Default")
      (node (ref "D14") (pin "24") (pinfunction "C_24") (pintype "passive"))
      (node (ref "D14") (pin "7") (pinfunction "C_7") (pintype "passive"))
      (node (ref "D15") (pin "24") (pinfunction "C_24") (pintype "passive"))
      (node (ref "D15") (pin "7") (pinfunction "C_7") (pintype "passive"))
      (node (ref "D16") (pin "24") (pinfunction "C_24") (pintype "passive"))
      (node (ref "D16") (pin "7") (pinfunction "C_7") (pintype "passive"))
      (node (ref "D17") (pin "24") (pinfunction "C_24") (pintype "passive"))
      (node (ref "D17") (pin "7") (pinfunction "C_7") (pintype "passive"))
      (node (ref "D18") (pin "24") (pinfunction "C_24") (pintype "passive"))
      (node (ref "D18") (pin "7") (pinfunction "C_7") (pintype "passive"))
      (node (ref "D19") (pin "24") (pinfunction "C_24") (pintype "passive"))
      (node (ref "D19") (pin "7") (pinfunction "C_7") (pintype "passive"))
      (node (ref "D2") (pin "24") (pinfunction "C_24") (pintype "passive"))
      (node (ref "D2") (pin "7") (pinfunction "C_7") (pintype "passive"))
      (node (ref "D20") (pin "24") (pinfunction "C_24") (pintype "passive"))
      (node (ref "D20") (pin "7") (pinfunction "C_7") (pintype "passive"))
      (node (ref "D21") (pin "24") (pinfunction "C_24") (pintype "passive"))
      (node (ref "D21") (pin "7") (pinfunction "C_7") (pintype "passive"))
      (node (ref "D22") (pin "24") (pinfunction "C_24") (pintype "passive"))
      (node (ref "D22") (pin "7") (pinfunction "C_7") (pintype "passive"))
      (node (ref "D23") (pin "24") (pinfunction "C_24") (pintype "passive"))
      (node (ref "D23") (pin "7") (pinfunction "C_7") (pintype "passive"))
      (node (ref "D24") (pin "24") (pinfunction "C_24") (pintype "passive"))
      (node (ref "D24") (pin "7") (pinfunction "C_7") (pintype "passive"))
      (node (ref "D25") (pin "24") (pinfunction "C_24") (pintype "passive"))
      (node (ref "D25") (pin "7") (pinfunction "C_7") (pintype "passive"))
      (node (ref "D26") (pin "24") (pinfunction "C_24") (pintype "passive"))
      (node (ref "D26") (pin "7") (pinfunction "C_7") (pintype "passive"))
      (node (ref "D27") (pin "24") (pinfunction "C_24") (pintype "passive"))
      (node (ref "D27") (pin "7") (pinfunction "C_7") (pintype "passive"))
      (node (ref "JP11") (pin "1") (pinfunction "1_1") (pintype "passive"))
      (node (ref "JP8") (pin "1") (pinfunction "1_1") (pintype "passive"))
    )
    (net (code "46") (name "SEG_C_SOURCE") (class "Default")
      (node (ref "JP10") (pin "1") (pinfunction "1_1") (pintype "passive"))
      (node (ref "M6") (pin "3") (pinfunction "D_3") (pintype "passive"))
    )
    (net (code "47") (name "SEG_D") (class "Default")
      (node (ref "D14") (pin "22") (pinfunction "D_22") (pintype "passive"))
      (node (ref "D14") (pin "5") (pinfunction "D_5") (pintype "passive"))
      (node (ref "D15") (pin "22") (pinfunction "D_22") (pintype "passive"))
      (node (ref "D15") (pin "5") (pinfunction "D_5") (pintype "passive"))
      (node (ref "D16") (pin "22") (pinfunction "D_22") (pintype "passive"))
      (node (ref "D16") (pin "5") (pinfunction "D_5") (pintype "passive"))
      (node (ref "D17") (pin "22") (pinfunction "D_22") (pintype "passive"))
      (node (ref "D17") (pin "5") (pinfunction "D_5") (pintype "passive"))
      (node (ref "D18") (pin "22") (pinfunction "D_22") (pintype "passive"))
      (node (ref "D18") (pin "5") (pinfunction "D_5") (pintype "passive"))
      (node (ref "D19") (pin "22") (pinfunction "D_22") (pintype "passive"))
      (node (ref "D19") (pin "5") (pinfunction "D_5") (pintype "passive"))
      (node (ref "D2") (pin "22") (pinfunction "D_22") (pintype "passive"))
      (node (ref "D2") (pin "5") (pinfunction "D_5") (pintype "passive"))
      (node (ref "D20") (pin "22") (pinfunction "D_22") (pintype "passive"))
      (node (ref "D20") (pin "5") (pinfunction "D_5") (pintype "passive"))
      (node (ref "D21") (pin "22") (pinfunction "D_22") (pintype "passive"))
      (node (ref "D21") (pin "5") (pinfunction "D_5") (pintype "passive"))
      (node (ref "D22") (pin "22") (pinfunction "D_22") (pintype "passive"))
      (node (ref "D22") (pin "5") (pinfunction "D_5") (pintype "passive"))
      (node (ref "D23") (pin "22") (pinfunction "D_22") (pintype "passive"))
      (node (ref "D23") (pin "5") (pinfunction "D_5") (pintype "passive"))
      (node (ref "D24") (pin "22") (pinfunction "D_22") (pintype "passive"))
      (node (ref "D24") (pin "5") (pinfunction "D_5") (pintype "passive"))
      (node (ref "D25") (pin "22") (pinfunction "D_22") (pintype "passive"))
      (node (ref "D25") (pin "5") (pinfunction "D_5") (pintype "passive"))
      (node (ref "D26") (pin "22") (pinfunction "D_22") (pintype "passive"))
      (node (ref "D26") (pin "5") (pinfunction "D_5") (pintype "passive"))
      (node (ref "D27") (pin "22") (pinfunction "D_22") (pintype "passive"))
      (node (ref "D27") (pin "5") (pinfunction "D_5") (pintype "passive"))
      (node (ref "M7") (pin "3") (pinfunction "D_3") (pintype "passive"))
    )
    (net (code "48") (name "SEG_DP") (class "Default")
      (node (ref "D14") (pin "25") (pinfunction "DP_25") (pintype "passive"))
      (node (ref "D14") (pin "6") (pinfunction "DP1_6") (pintype "passive"))
      (node (ref "D14") (pin "8") (pinfunction "DP_8") (pintype "passive"))
      (node (ref "D15") (pin "25") (pinfunction "DP_25") (pintype "passive"))
      (node (ref "D15") (pin "6") (pinfunction "DP1_6") (pintype "passive"))
      (node (ref "D15") (pin "8") (pinfunction "DP_8") (pintype "passive"))
      (node (ref "D16") (pin "25") (pinfunction "DP_25") (pintype "passive"))
      (node (ref "D16") (pin "6") (pinfunction "DP1_6") (pintype "passive"))
      (node (ref "D16") (pin "8") (pinfunction "DP_8") (pintype "passive"))
      (node (ref "D17") (pin "25") (pinfunction "DP_25") (pintype "passive"))
      (node (ref "D17") (pin "6") (pinfunction "DP1_6") (pintype "passive"))
      (node (ref "D17") (pin "8") (pinfunction "DP_8") (pintype "passive"))
      (node (ref "D18") (pin "25") (pinfunction "DP_25") (pintype "passive"))
      (node (ref "D18") (pin "6") (pinfunction "DP1_6") (pintype "passive"))
      (node (ref "D18") (pin "8") (pinfunction "DP_8") (pintype "passive"))
      (node (ref "D19") (pin "25") (pinfunction "DP_25") (pintype "passive"))
      (node (ref "D19") (pin "6") (pinfunction "DP1_6") (pintype "passive"))
      (node (ref "D19") (pin "8") (pinfunction "DP_8") (pintype "passive"))
      (node (ref "D2") (pin "25") (pinfunction "DP_25") (pintype "passive"))
      (node (ref "D2") (pin "6") (pinfunction "DP1_6") (pintype "passive"))
      (node (ref "D2") (pin "8") (pinfunction "DP_8") (pintype "passive"))
      (node (ref "D20") (pin "25") (pinfunction "DP_25") (pintype "passive"))
      (node (ref "D20") (pin "6") (pinfunction "DP1_6") (pintype "passive"))
      (node (ref "D20") (pin "8") (pinfunction "DP_8") (pintype "passive"))
      (node (ref "D21") (pin "25") (pinfunction "DP_25") (pintype "passive"))
      (node (ref "D21") (pin "6") (pinfunction "DP1_6") (pintype "passive"))
      (node (ref "D21") (pin "8") (pinfunction "DP_8") (pintype "passive"))
      (node (ref "D22") (pin "25") (pinfunction "DP_25") (pintype "passive"))
      (node (ref "D22") (pin "6") (pinfunction "DP1_6") (pintype "passive"))
      (node (ref "D22") (pin "8") (pinfunction "DP_8") (pintype "passive"))
      (node (ref "D23") (pin "25") (pinfunction "DP_25") (pintype "passive"))
      (node (ref "D23") (pin "6") (pinfunction "DP1_6") (pintype "passive"))
      (node (ref "D23") (pin "8") (pinfunction "DP_8") (pintype "passive"))
      (node (ref "D24") (pin "25") (pinfunction "DP_25") (pintype "passive"))
      (node (ref "D24") (pin "6") (pinfunction "DP1_6") (pintype "passive"))
      (node (ref "D24") (pin "8") (pinfunction "DP_8") (pintype "passive"))
      (node (ref "D25") (pin "25") (pinfunction "DP_25") (pintype "passive"))
      (node (ref "D25") (pin "6") (pinfunction "DP1_6") (pintype "passive"))
      (node (ref "D25") (pin "8") (pinfunction "DP_8") (pintype "passive"))
      (node (ref "D26") (pin "25") (pinfunction "DP_25") (pintype "passive"))
      (node (ref "D26") (pin "6") (pinfunction "DP1_6") (pintype "passive"))
      (node (ref "D26") (pin "8") (pinfunction "DP_8") (pintype "passive"))
      (node (ref "D27") (pin "25") (pinfunction "DP_25") (pintype "passive"))
      (node (ref "D27") (pin "6") (pinfunction "DP1_6") (pintype "passive"))
      (node (ref "D27") (pin "8") (pinfunction "DP_8") (pintype "passive"))
      (node (ref "JP12") (pin "1") (pinfunction "1_1") (pintype "passive"))
      (node (ref "JP9") (pin "1") (pinfunction "1_1") (pintype "passive"))
    )
    (net (code "49") (name "SEG_DP_SOURCE") (class "Default")
      (node (ref "JP7") (pin "1") (pinfunction "1_1") (pintype "passive"))
      (node (ref "M11") (pin "3") (pinfunction "D_3") (pintype "passive"))
    )
    (net (code "50") (name "SEG_E") (class "Default")
      (node (ref "D14") (pin "21") (pinfunction "E_21") (pintype "passive"))
      (node (ref "D14") (pin "4") (pinfunction "E_4") (pintype "passive"))
      (node (ref "D15") (pin "21") (pinfunction "E_21") (pintype "passive"))
      (node (ref "D15") (pin "4") (pinfunction "E_4") (pintype "passive"))
      (node (ref "D16") (pin "21") (pinfunction "E_21") (pintype "passive"))
      (node (ref "D16") (pin "4") (pinfunction "E_4") (pintype "passive"))
      (node (ref "D17") (pin "21") (pinfunction "E_21") (pintype "passive"))
      (node (ref "D17") (pin "4") (pinfunction "E_4") (pintype "passive"))
      (node (ref "D18") (pin "21") (pinfunction "E_21") (pintype "passive"))
      (node (ref "D18") (pin "4") (pinfunction "E_4") (pintype "passive"))
      (node (ref "D19") (pin "21") (pinfunction "E_21") (pintype "passive"))
      (node (ref "D19") (pin "4") (pinfunction "E_4") (pintype "passive"))
      (node (ref "D2") (pin "21") (pinfunction "E_21") (pintype "passive"))
      (node (ref "D2") (pin "4") (pinfunction "E_4") (pintype "passive"))
      (node (ref "D20") (pin "21") (pinfunction "E_21") (pintype "passive"))
      (node (ref "D20") (pin "4") (pinfunction "E_4") (pintype "passive"))
      (node (ref "D21") (pin "21") (pinfunction "E_21") (pintype "passive"))
      (node (ref "D21") (pin "4") (pinfunction "E_4") (pintype "passive"))
      (node (ref "D22") (pin "21") (pinfunction "E_21") (pintype "passive"))
      (node (ref "D22") (pin "4") (pinfunction "E_4") (pintype "passive"))
      (node (ref "D23") (pin "21") (pinfunction "E_21") (pintype "passive"))
      (node (ref "D23") (pin "4") (pinfunction "E_4") (pintype "passive"))
      (node (ref "D24") (pin "21") (pinfunction "E_21") (pintype "passive"))
      (node (ref "D24") (pin "4") (pinfunction "E_4") (pintype "passive"))
      (node (ref "D25") (pin "21") (pinfunction "E_21") (pintype "passive"))
      (node (ref "D25") (pin "4") (pinfunction "E_4") (pintype "passive"))
      (node (ref "D26") (pin "21") (pinfunction "E_21") (pintype "passive"))
      (node (ref "D26") (pin "4") (pinfunction "E_4") (pintype "passive"))
      (node (ref "D27") (pin "21") (pinfunction "E_21") (pintype "passive"))
      (node (ref "D27") (pin "4") (pinfunction "E_4") (pintype "passive"))
      (node (ref "M8") (pin "3") (pinfunction "D_3") (pintype "passive"))
    )
    (net (code "51") (name "SEG_F") (class "Default")
      (node (ref "D14") (pin "2") (pinfunction "F_2") (pintype "passive"))
      (node (ref "D14") (pin "29") (pinfunction "F_29") (pintype "passive"))
      (node (ref "D15") (pin "2") (pinfunction "F_2") (pintype "passive"))
      (node (ref "D15") (pin "29") (pinfunction "F_29") (pintype "passive"))
      (node (ref "D16") (pin "2") (pinfunction "F_2") (pintype "passive"))
      (node (ref "D16") (pin "29") (pinfunction "F_29") (pintype "passive"))
      (node (ref "D17") (pin "2") (pinfunction "F_2") (pintype "passive"))
      (node (ref "D17") (pin "29") (pinfunction "F_29") (pintype "passive"))
      (node (ref "D18") (pin "2") (pinfunction "F_2") (pintype "passive"))
      (node (ref "D18") (pin "29") (pinfunction "F_29") (pintype "passive"))
      (node (ref "D19") (pin "2") (pinfunction "F_2") (pintype "passive"))
      (node (ref "D19") (pin "29") (pinfunction "F_29") (pintype "passive"))
      (node (ref "D2") (pin "2") (pinfunction "F_2") (pintype "passive"))
      (node (ref "D2") (pin "29") (pinfunction "F_29") (pintype "passive"))
      (node (ref "D20") (pin "2") (pinfunction "F_2") (pintype "passive"))
      (node (ref "D20") (pin "29") (pinfunction "F_29") (pintype "passive"))
      (node (ref "D21") (pin "2") (pinfunction "F_2") (pintype "passive"))
      (node (ref "D21") (pin "29") (pinfunction "F_29") (pintype "passive"))
      (node (ref "D22") (pin "2") (pinfunction "F_2") (pintype "passive"))
      (node (ref "D22") (pin "29") (pinfunction "F_29") (pintype "passive"))
      (node (ref "D23") (pin "2") (pinfunction "F_2") (pintype "passive"))
      (node (ref "D23") (pin "29") (pinfunction "F_29") (pintype "passive"))
      (node (ref "D24") (pin "2") (pinfunction "F_2") (pintype "passive"))
      (node (ref "D24") (pin "29") (pinfunction "F_29") (pintype "passive"))
      (node (ref "D25") (pin "2") (pinfunction "F_2") (pintype "passive"))
      (node (ref "D25") (pin "29") (pinfunction "F_29") (pintype "passive"))
      (node (ref "D26") (pin "2") (pinfunction "F_2") (pintype "passive"))
      (node (ref "D26") (pin "29") (pinfunction "F_29") (pintype "passive"))
      (node (ref "D27") (pin "2") (pinfunction "F_2") (pintype "passive"))
      (node (ref "D27") (pin "29") (pinfunction "F_29") (pintype "passive"))
      (node (ref "M9") (pin "3") (pinfunction "D_3") (pintype "passive"))
    )
    (net (code "52") (name "SEG_G") (class "Default")
      (node (ref "D14") (pin "1") (pinfunction "G1_1") (pintype "passive"))
      (node (ref "D14") (pin "3") (pinfunction "G_3") (pintype "passive"))
      (node (ref "D14") (pin "30") (pinfunction "G_30") (pintype "passive"))
      (node (ref "D15") (pin "1") (pinfunction "G1_1") (pintype "passive"))
      (node (ref "D15") (pin "3") (pinfunction "G_3") (pintype "passive"))
      (node (ref "D15") (pin "30") (pinfunction "G_30") (pintype "passive"))
      (node (ref "D16") (pin "1") (pinfunction "G1_1") (pintype "passive"))
      (node (ref "D16") (pin "3") (pinfunction "G_3") (pintype "passive"))
      (node (ref "D16") (pin "30") (pinfunction "G_30") (pintype "passive"))
      (node (ref "D17") (pin "1") (pinfunction "G1_1") (pintype "passive"))
      (node (ref "D17") (pin "3") (pinfunction "G_3") (pintype "passive"))
      (node (ref "D17") (pin "30") (pinfunction "G_30") (pintype "passive"))
      (node (ref "D18") (pin "1") (pinfunction "G1_1") (pintype "passive"))
      (node (ref "D18") (pin "3") (pinfunction "G_3") (pintype "passive"))
      (node (ref "D18") (pin "30") (pinfunction "G_30") (pintype "passive"))
      (node (ref "D19") (pin "1") (pinfunction "G1_1") (pintype "passive"))
      (node (ref "D19") (pin "3") (pinfunction "G_3") (pintype "passive"))
      (node (ref "D19") (pin "30") (pinfunction "G_30") (pintype "passive"))
      (node (ref "D2") (pin "1") (pinfunction "G1_1") (pintype "passive"))
      (node (ref "D2") (pin "3") (pinfunction "G_3") (pintype "passive"))
      (node (ref "D2") (pin "30") (pinfunction "G_30") (pintype "passive"))
      (node (ref "D20") (pin "1") (pinfunction "G1_1") (pintype "passive"))
      (node (ref "D20") (pin "3") (pinfunction "G_3") (pintype "passive"))
      (node (ref "D20") (pin "30") (pinfunction "G_30") (pintype "passive"))
      (node (ref "D21") (pin "1") (pinfunction "G1_1") (pintype "passive"))
      (node (ref "D21") (pin "3") (pinfunction "G_3") (pintype "passive"))
      (node (ref "D21") (pin "30") (pinfunction "G_30") (pintype "passive"))
      (node (ref "D22") (pin "1") (pinfunction "G1_1") (pintype "passive"))
      (node (ref "D22") (pin "3") (pinfunction "G_3") (pintype "passive"))
      (node (ref "D22") (pin "30") (pinfunction "G_30") (pintype "passive"))
      (node (ref "D23") (pin "1") (pinfunction "G1_1") (pintype "passive"))
      (node (ref "D23") (pin "3") (pinfunction "G_3") (pintype "passive"))
      (node (ref "D23") (pin "30") (pinfunction "G_30") (pintype "passive"))
      (node (ref "D24") (pin "1") (pinfunction "G1_1") (pintype "passive"))
      (node (ref "D24") (pin "3") (pinfunction "G_3") (pintype "passive"))
      (node (ref "D24") (pin "30") (pinfunction "G_30") (pintype "passive"))
      (node (ref "D25") (pin "1") (pinfunction "G1_1") (pintype "passive"))
      (node (ref "D25") (pin "3") (pinfunction "G_3") (pintype "passive"))
      (node (ref "D25") (pin "30") (pinfunction "G_30") (pintype "passive"))
      (node (ref "D26") (pin "1") (pinfunction "G1_1") (pintype "passive"))
      (node (ref "D26") (pin "3") (pinfunction "G_3") (pintype "passive"))
      (node (ref "D26") (pin "30") (pinfunction "G_30") (pintype "passive"))
      (node (ref "D27") (pin "1") (pinfunction "G1_1") (pintype "passive"))
      (node (ref "D27") (pin "3") (pinfunction "G_3") (pintype "passive"))
      (node (ref "D27") (pin "30") (pinfunction "G_30") (pintype "passive"))
      (node (ref "M10") (pin "3") (pinfunction "D_3") (pintype "passive"))
    )
  )
)
